# CAN_TxRx.net
KiCad netlist of a schematic drawn in Altium Designer
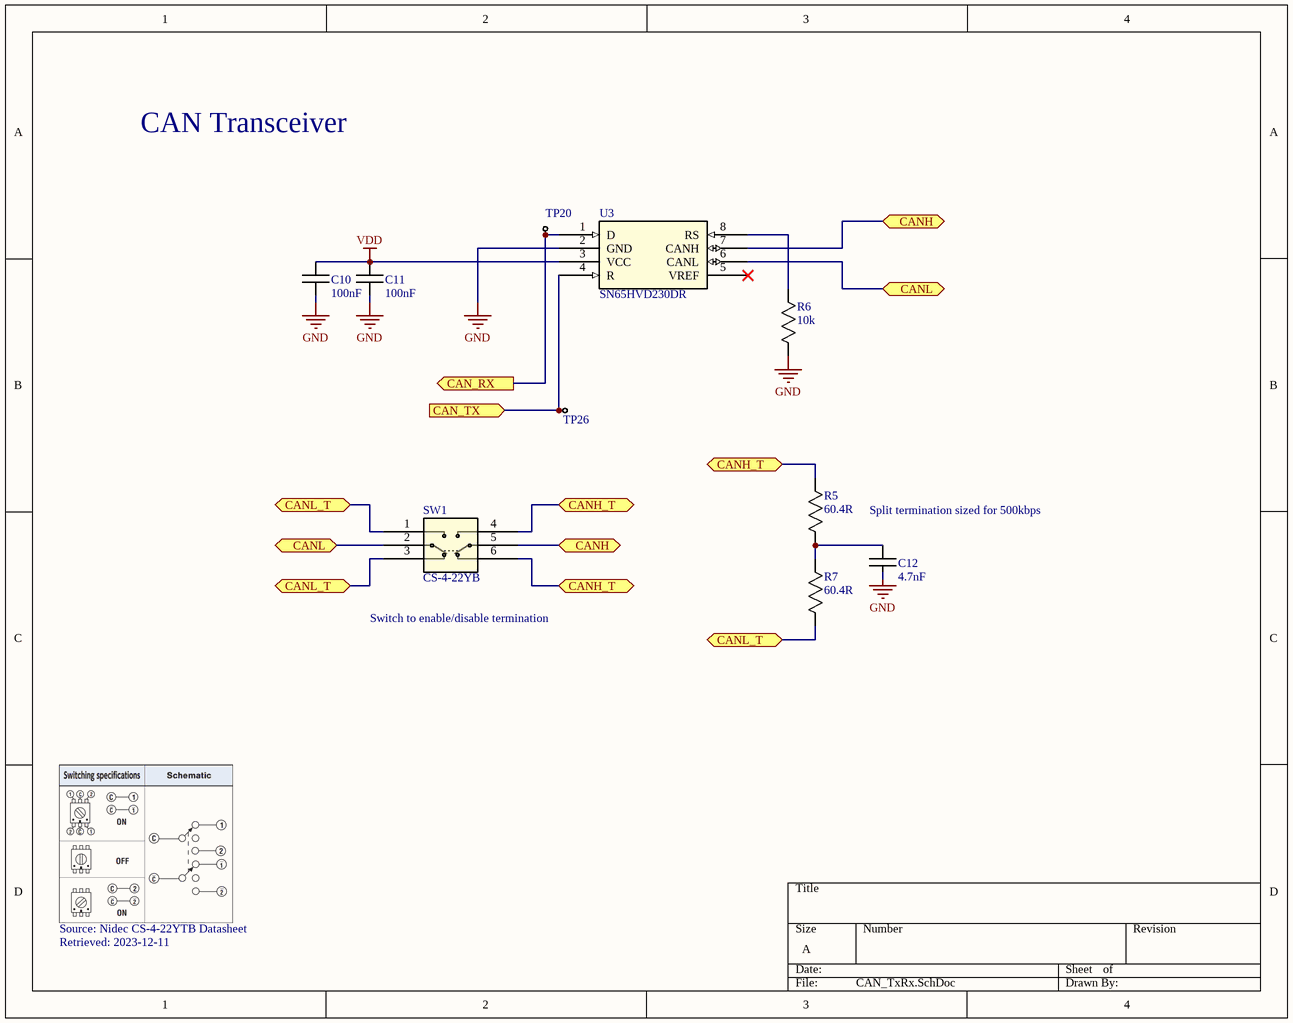
[diagram p0: CAN_TxRx.SchDoc]

(export (version "E")
  (design (tool "Eeschema 10.0.6"))
  (components
    (comp (ref "C10")
      (value "100nF")
      (footprint "CAP0805")
      (description "Multilayer Ceramic Capacitor, 0.1 uF, 50 V, ± 10%, X7R, 0805 [2012 Metric]")
      (fields
        (field (name "MANUFACTURER") "Yageo")
        (field (name "MANUFACTURER PART NUMBER") "CC0805KRX7R9BB104")
      )
      (libsource (lib "Schlib1") (part "CC0805KRX7R9BB104"))
    )
    (comp (ref "C11")
      (value "100nF")
      (footprint "CAP0805")
      (description "Multilayer Ceramic Capacitor, 0.1 uF, 50 V, ± 10%, X7R, 0805 [2012 Metric]")
      (fields
        (field (name "MANUFACTURER") "Yageo")
        (field (name "MANUFACTURER PART NUMBER") "CC0805KRX7R9BB104")
      )
      (libsource (lib "Schlib1") (part "CC0805KRX7R9BB104"))
    )
    (comp (ref "C12")
      (value "4.7nF")
      (footprint "C0603")
      (description "Cap Cer 0603 4.7NF 100VDC X8G")
      (fields
        (field (name "MANUFACTURER") "KEMET")
        (field (name "MANUFACTURER PART NUMBER") "C0603C472K1TACAUTO")
      )
      (libsource (lib "Schlib1") (part "C0603C472K1TACAUTO"))
    )
    (comp (ref "R5")
      (value "60.4R")
      (footprint "R0603")
      (description "Res Thick Film 0603 60.4 Ohm 1% 0.1W(1/10W) ±100ppm/C Pad SMD T/R")
      (fields
        (field (name "MANUFACTURER") "Yageo")
        (field (name "MANUFACTURER PART NUMBER") "RC0603FR-0760R4L")
      )
      (libsource (lib "Schlib1") (part "RC0603FR-0760R4L"))
    )
    (comp (ref "R6")
      (value "10k")
      (footprint "R0603")
      (description "SMD Chip Resistor, 10 kOhm, ± 5%, 100 mW, 0603 [1608 Metric], Thick Film, General Purpose")
      (fields
        (field (name "MANUFACTURER") "Yageo")
        (field (name "MANUFACTURER PART NUMBER") "RC0603JR-0710KL")
      )
      (libsource (lib "Schlib1") (part "RC0603JR-0710KL"))
    )
    (comp (ref "R7")
      (value "60.4R")
      (footprint "R0603")
      (description "Res Thick Film 0603 60.4 Ohm 1% 0.1W(1/10W) ±100ppm/C Pad SMD T/R")
      (fields
        (field (name "MANUFACTURER") "Yageo")
        (field (name "MANUFACTURER PART NUMBER") "RC0603FR-0760R4L")
      )
      (libsource (lib "Schlib1") (part "RC0603FR-0760R4L"))
    )
    (comp (ref "SW1")
      (value "CS-4-22YB")
      (footprint "CS-4-22YB_NDC")
      (description "Switch Rotary ON OFF ON DPDT 2 Flush Screwdriver Gull Wing 0.1A 16VAC 16VDC 0.5VA T/R")
      (fields
        (field (name "MANUFACTURER") "Nidec Copal")
        (field (name "MANUFACTURER PART NUMBER") "CS-4-22YTB")
        (field (name "COPYRIGHT") "Copyright (C) 2023 Ultra Librarian. All rights reserved.")
      )
      (libsource (lib "Schlib1") (part "CS-4-22YTB"))
    )
    (comp (ref "TP20")
      (value "1mm Test Point")
      (footprint "TP_1MM")
      (libsource (lib "Schlib1") (part "TestPoint_1mm"))
    )
    (comp (ref "TP26")
      (value "1mm Test Point")
      (footprint "TP_1MM")
      (libsource (lib "Schlib1") (part "TestPoint_1mm"))
    )
    (comp (ref "U3")
      (value "SN65HVD230DR")
      (footprint "SOIC_8")
      (description "EAR99 65HVD230 Cut Tape (CT) CANbus interface driver 3.3V 17mA 72.603129mg 1Mbps")
      (fields (field (name "MANUFACTURER") "Texas Instruments") (field (name "LCSC PART#") "C12084"))
      (libsource (lib "Schlib1") (part "SN65HVD230DR"))
    )
  )
  (nets
    (net (code "1") (name "/CANH") (class "Default")
      (node (ref "SW1") (pin "5") (pinfunction "5_5") (pintype "passive"))
      (node (ref "U3") (pin "7") (pinfunction "CANH_7") (pintype "bidirectional"))
    )
    (net (code "2") (name "/CANH_T") (class "Default")
      (node (ref "R5") (pin "1") (pinfunction "1_1") (pintype "passive"))
      (node (ref "SW1") (pin "4") (pinfunction "4_4") (pintype "passive"))
      (node (ref "SW1") (pin "6") (pinfunction "6_6") (pintype "passive"))
    )
    (net (code "3") (name "/CANL") (class "Default")
      (node (ref "SW1") (pin "2") (pinfunction "2_2") (pintype "passive"))
      (node (ref "U3") (pin "6") (pinfunction "CANL_6") (pintype "bidirectional"))
    )
    (net (code "4") (name "/CANL_T") (class "Default")
      (node (ref "R7") (pin "2") (pinfunction "2_2") (pintype "passive"))
      (node (ref "SW1") (pin "1") (pinfunction "1_1") (pintype "passive"))
      (node (ref "SW1") (pin "3") (pinfunction "3_3") (pintype "passive"))
    )
    (net (code "5") (name "/CAN_RX") (class "Default")
      (node (ref "TP20") (pin "1") (pinfunction "0_1") (pintype "passive"))
      (node (ref "U3") (pin "1") (pinfunction "D_1") (pintype "input"))
    )
    (net (code "6") (name "/CAN_TX") (class "Default")
      (node (ref "TP26") (pin "1") (pinfunction "0_1") (pintype "passive"))
      (node (ref "U3") (pin "4") (pinfunction "R_4") (pintype "input"))
    )
    (net (code "7") (name "GND") (class "Default")
      (node (ref "C10") (pin "2") (pinfunction "2_2") (pintype "passive"))
      (node (ref "C11") (pin "2") (pinfunction "2_2") (pintype "passive"))
      (node (ref "C12") (pin "2") (pinfunction "2_2") (pintype "passive"))
      (node (ref "R6") (pin "2") (pinfunction "2_2") (pintype "passive"))
      (node (ref "U3") (pin "2") (pinfunction "GND_2") (pintype "power_in"))
    )
    (net (code "8") (name "Net-(C12-Pad1)") (class "Default")
      (node (ref "C12") (pin "1") (pinfunction "1_1") (pintype "passive"))
      (node (ref "R5") (pin "2") (pinfunction "2_2") (pintype "passive"))
      (node (ref "R7") (pin "1") (pinfunction "1_1") (pintype "passive"))
    )
    (net (code "9") (name "Net-(U3-RS)") (class "Default")
      (node (ref "R6") (pin "1") (pinfunction "1_1") (pintype "passive"))
      (node (ref "U3") (pin "8") (pinfunction "RS_8") (pintype "input"))
    )
    (net (code "10") (name "VDD") (class "Default")
      (node (ref "C10") (pin "1") (pinfunction "1_1") (pintype "passive"))
      (node (ref "C11") (pin "1") (pinfunction "1_1") (pintype "passive"))
      (node (ref "U3") (pin "3") (pinfunction "VCC_3") (pintype "power_in"))
    )
    (net (code "11") (name "unconnected-(U3-VREF-Pad5)") (class "Default")
      (node (ref "U3") (pin "5") (pinfunction "VREF_5") (pintype "power_in+no_connect"))
    )
  )
)
